# TestPointOfUnusedPCIe.net
KiCad netlist of a schematic drawn in Altium Designer
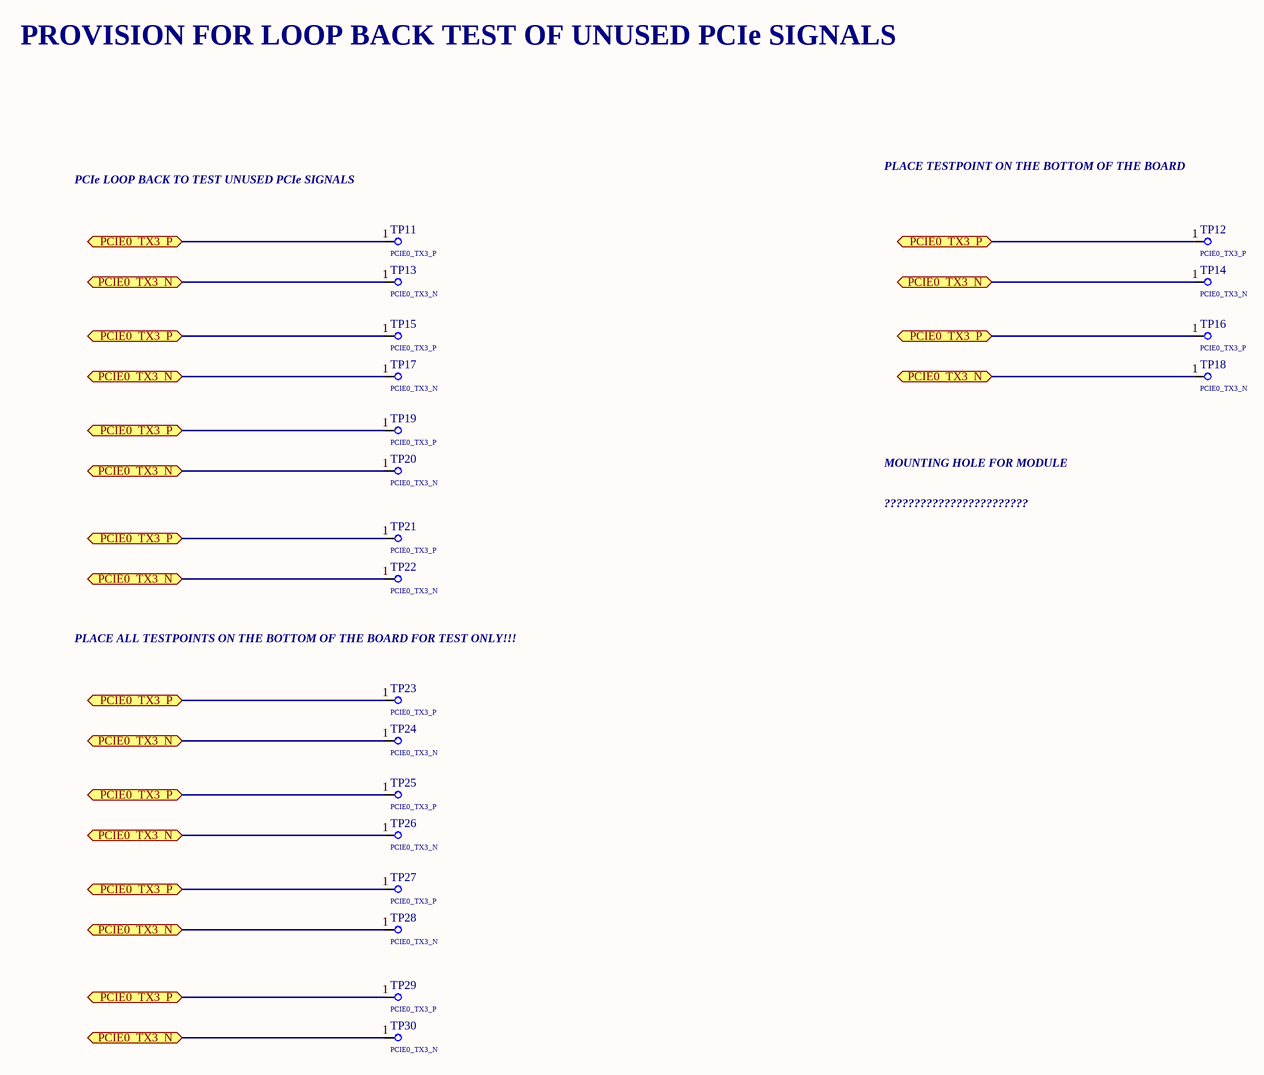
[diagram p0: TestPointOfUnusedPCIe.SchDoc]

(export (version "E")
  (design (tool "Eeschema 10.0.6"))
  (components
    (comp (ref "TP11")
      (value "PCIE0_TX3_P")
      (footprint "TestPoint_Pad_D1.0mm")
      (libsource (lib "GM_Altium_Library") (part "TestPoint_D1mm"))
    )
    (comp (ref "TP12")
      (value "PCIE0_TX3_P")
      (footprint "TestPoint_Pad_D1.0mm")
      (libsource (lib "GM_Altium_Library") (part "TestPoint_D1mm"))
    )
    (comp (ref "TP13")
      (value "PCIE0_TX3_N")
      (footprint "TestPoint_Pad_D1.0mm")
      (libsource (lib "GM_Altium_Library") (part "TestPoint_D1mm"))
    )
    (comp (ref "TP14")
      (value "PCIE0_TX3_N")
      (footprint "TestPoint_Pad_D1.0mm")
      (libsource (lib "GM_Altium_Library") (part "TestPoint_D1mm"))
    )
    (comp (ref "TP15")
      (value "PCIE0_TX3_P")
      (footprint "TestPoint_Pad_D1.0mm")
      (libsource (lib "GM_Altium_Library") (part "TestPoint_D1mm"))
    )
    (comp (ref "TP16")
      (value "PCIE0_TX3_P")
      (footprint "TestPoint_Pad_D1.0mm")
      (libsource (lib "GM_Altium_Library") (part "TestPoint_D1mm"))
    )
    (comp (ref "TP17")
      (value "PCIE0_TX3_N")
      (footprint "TestPoint_Pad_D1.0mm")
      (libsource (lib "GM_Altium_Library") (part "TestPoint_D1mm"))
    )
    (comp (ref "TP18")
      (value "PCIE0_TX3_N")
      (footprint "TestPoint_Pad_D1.0mm")
      (libsource (lib "GM_Altium_Library") (part "TestPoint_D1mm"))
    )
    (comp (ref "TP19")
      (value "PCIE0_TX3_P")
      (footprint "TestPoint_Pad_D1.0mm")
      (libsource (lib "GM_Altium_Library") (part "TestPoint_D1mm"))
    )
    (comp (ref "TP20")
      (value "PCIE0_TX3_N")
      (footprint "TestPoint_Pad_D1.0mm")
      (libsource (lib "GM_Altium_Library") (part "TestPoint_D1mm"))
    )
    (comp (ref "TP21")
      (value "PCIE0_TX3_P")
      (footprint "TestPoint_Pad_D1.0mm")
      (libsource (lib "GM_Altium_Library") (part "TestPoint_D1mm"))
    )
    (comp (ref "TP22")
      (value "PCIE0_TX3_N")
      (footprint "TestPoint_Pad_D1.0mm")
      (libsource (lib "GM_Altium_Library") (part "TestPoint_D1mm"))
    )
    (comp (ref "TP23")
      (value "PCIE0_TX3_P")
      (footprint "TestPoint_Pad_D1.0mm")
      (libsource (lib "GM_Altium_Library") (part "TestPoint_D1mm"))
    )
    (comp (ref "TP24")
      (value "PCIE0_TX3_N")
      (footprint "TestPoint_Pad_D1.0mm")
      (libsource (lib "GM_Altium_Library") (part "TestPoint_D1mm"))
    )
    (comp (ref "TP25")
      (value "PCIE0_TX3_P")
      (footprint "TestPoint_Pad_D1.0mm")
      (libsource (lib "GM_Altium_Library") (part "TestPoint_D1mm"))
    )
    (comp (ref "TP26")
      (value "PCIE0_TX3_N")
      (footprint "TestPoint_Pad_D1.0mm")
      (libsource (lib "GM_Altium_Library") (part "TestPoint_D1mm"))
    )
    (comp (ref "TP27")
      (value "PCIE0_TX3_P")
      (footprint "TestPoint_Pad_D1.0mm")
      (libsource (lib "GM_Altium_Library") (part "TestPoint_D1mm"))
    )
    (comp (ref "TP28")
      (value "PCIE0_TX3_N")
      (footprint "TestPoint_Pad_D1.0mm")
      (libsource (lib "GM_Altium_Library") (part "TestPoint_D1mm"))
    )
    (comp (ref "TP29")
      (value "PCIE0_TX3_P")
      (footprint "TestPoint_Pad_D1.0mm")
      (libsource (lib "GM_Altium_Library") (part "TestPoint_D1mm"))
    )
    (comp (ref "TP30")
      (value "PCIE0_TX3_N")
      (footprint "TestPoint_Pad_D1.0mm")
      (libsource (lib "GM_Altium_Library") (part "TestPoint_D1mm"))
    )
  )
  (nets
    (net (code "1") (name "/PCIE0_TX3_N") (class "Default")
      (node (ref "TP13") (pin "1") (pinfunction "1_1") (pintype "passive"))
      (node (ref "TP14") (pin "1") (pinfunction "1_1") (pintype "passive"))
      (node (ref "TP17") (pin "1") (pinfunction "1_1") (pintype "passive"))
      (node (ref "TP18") (pin "1") (pinfunction "1_1") (pintype "passive"))
      (node (ref "TP20") (pin "1") (pinfunction "1_1") (pintype "passive"))
      (node (ref "TP22") (pin "1") (pinfunction "1_1") (pintype "passive"))
      (node (ref "TP24") (pin "1") (pinfunction "1_1") (pintype "passive"))
      (node (ref "TP26") (pin "1") (pinfunction "1_1") (pintype "passive"))
      (node (ref "TP28") (pin "1") (pinfunction "1_1") (pintype "passive"))
      (node (ref "TP30") (pin "1") (pinfunction "1_1") (pintype "passive"))
    )
    (net (code "2") (name "/PCIE0_TX3_P") (class "Default")
      (node (ref "TP11") (pin "1") (pinfunction "1_1") (pintype "passive"))
      (node (ref "TP12") (pin "1") (pinfunction "1_1") (pintype "passive"))
      (node (ref "TP15") (pin "1") (pinfunction "1_1") (pintype "passive"))
      (node (ref "TP16") (pin "1") (pinfunction "1_1") (pintype "passive"))
      (node (ref "TP19") (pin "1") (pinfunction "1_1") (pintype "passive"))
      (node (ref "TP21") (pin "1") (pinfunction "1_1") (pintype "passive"))
      (node (ref "TP23") (pin "1") (pinfunction "1_1") (pintype "passive"))
      (node (ref "TP25") (pin "1") (pinfunction "1_1") (pintype "passive"))
      (node (ref "TP27") (pin "1") (pinfunction "1_1") (pintype "passive"))
      (node (ref "TP29") (pin "1") (pinfunction "1_1") (pintype "passive"))
    )
  )
)
